# PIR_Sensor.net
KiCad netlist of a schematic drawn in Altium Designer
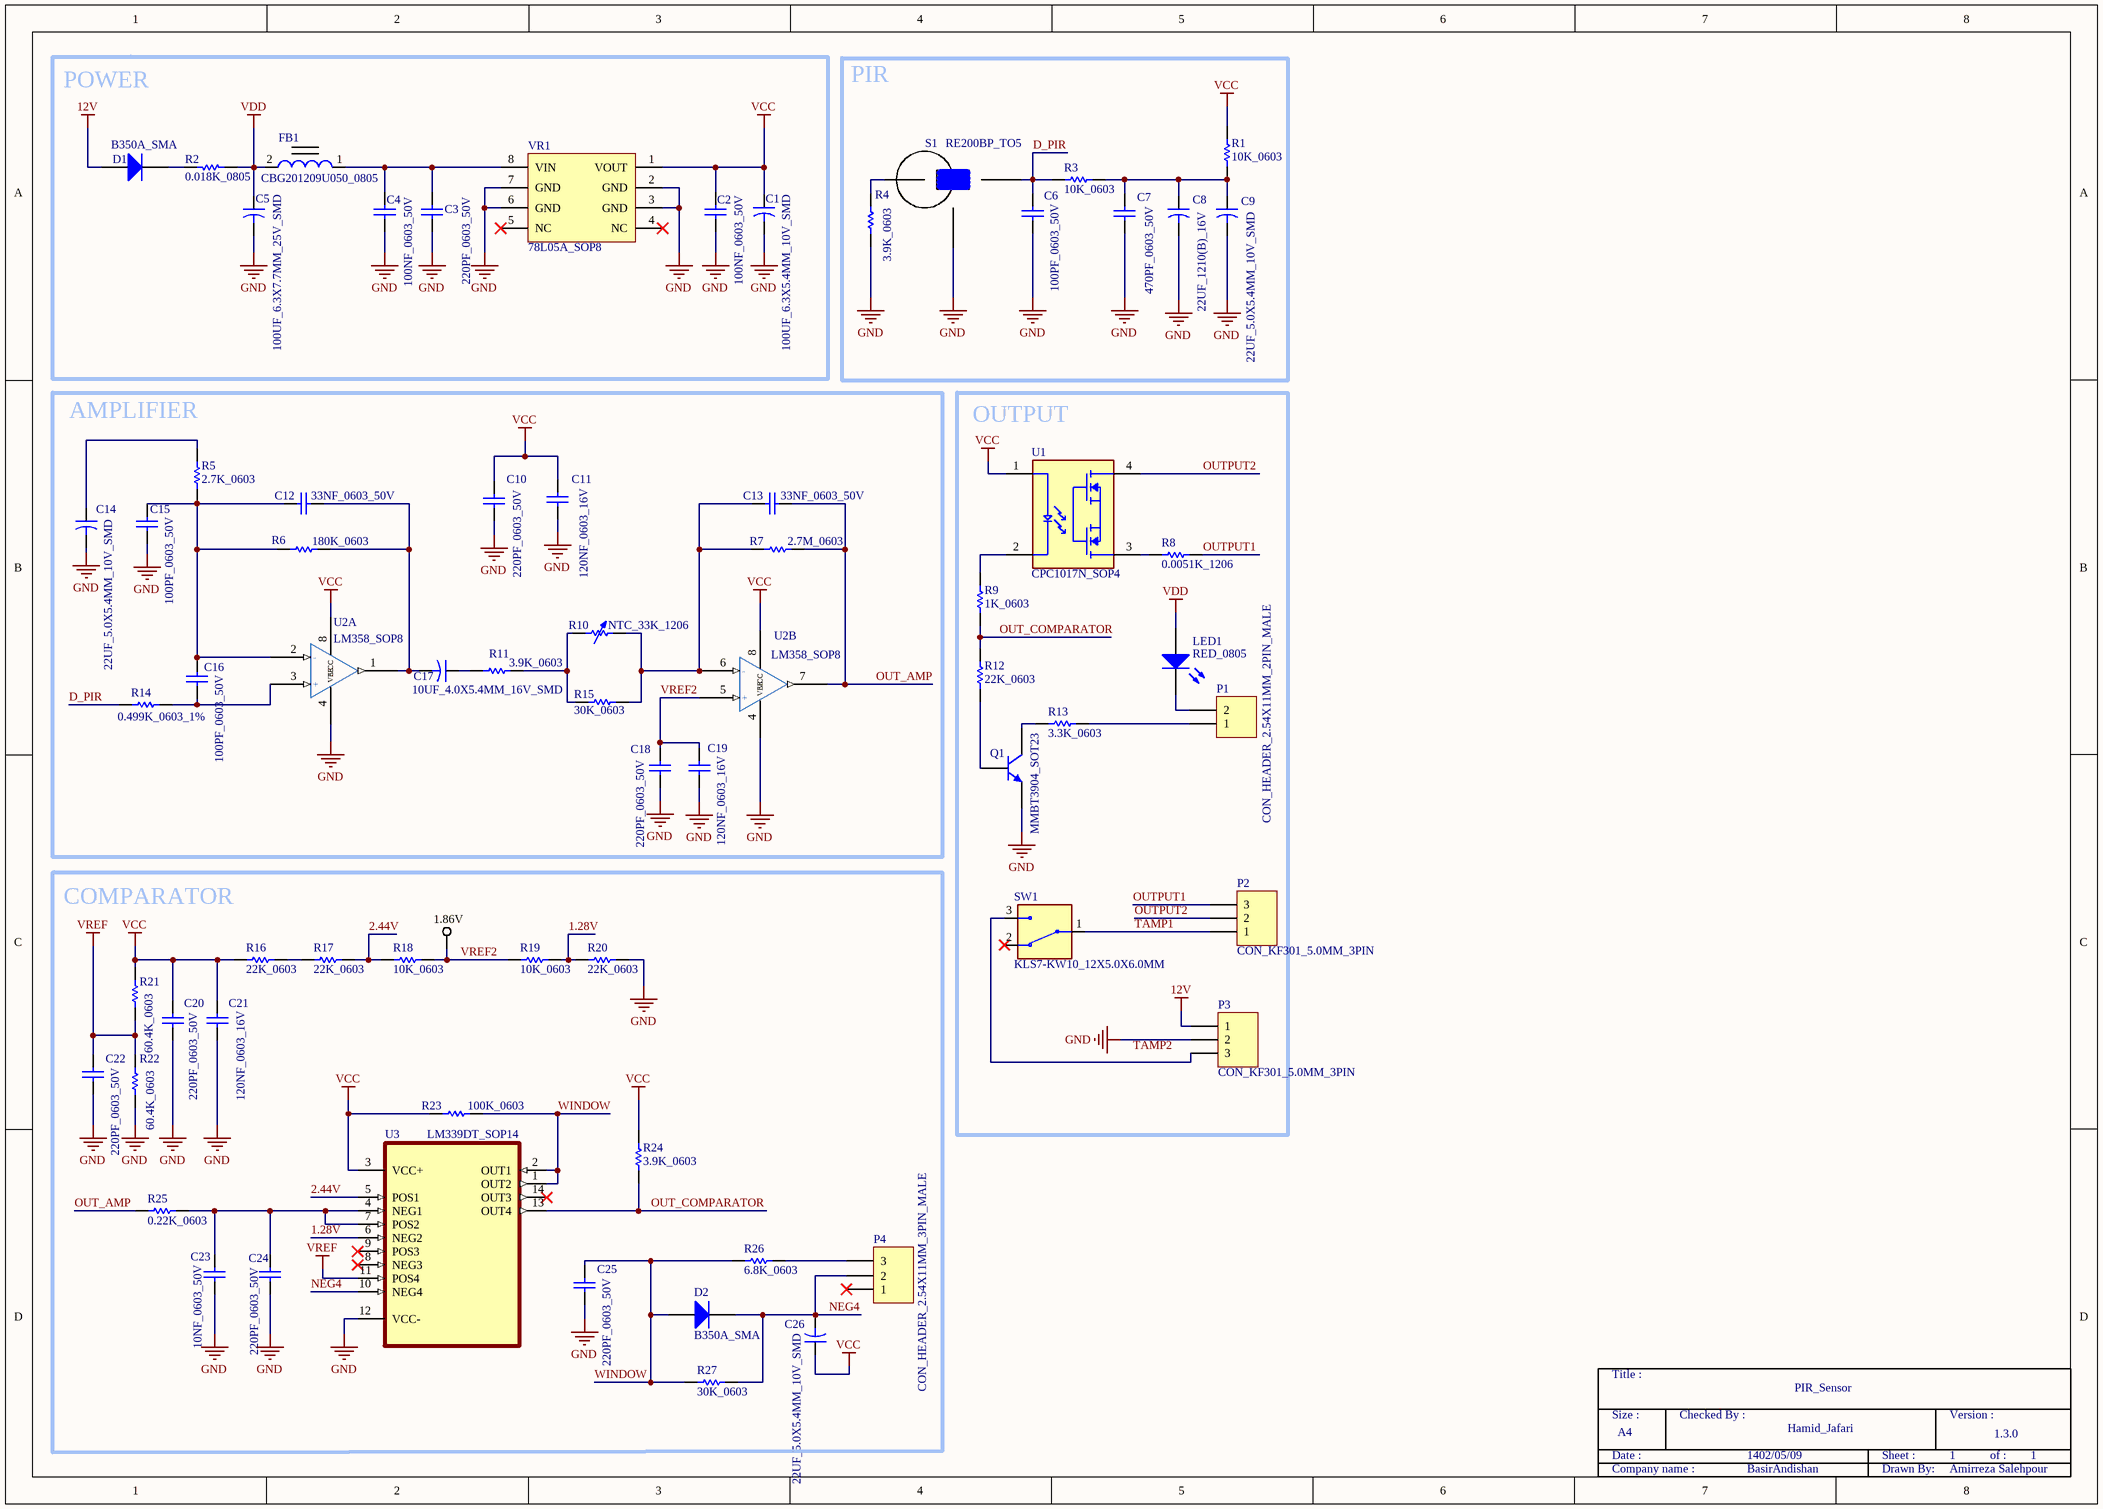
[diagram p0: PIR_Sensor.SchDoc]

(export (version "E")
  (design (tool "Eeschema 10.0.6"))
  (components
    (comp (ref "1.86V")
      (value "TESTPOINT_SMD")
      (footprint "TPSMD_C1")
      (description "TEST POINT")
      (fields (field (name "MANF") "MANF") (field (name "MANF_P#") "MANF_P#"))
      (libsource (lib "GTC Shem") (part "TESTPOINT_SMD"))
    )
    (comp (ref "C1")
      (value "100UF_6.3X5.4MM_10V_SMD")
      (footprint "CAP_EL_SMD_6X8")
      (libsource (lib "GTC Shem") (part "Cap_Electrical"))
    )
    (comp (ref "C2")
      (value "100NF_0603_50V")
      (footprint "Cap_0603_Nominal")
      (description "0603")
      (libsource (lib "GTC Shem") (part "Cap"))
    )
    (comp (ref "C3")
      (value "220PF_0603_50V")
      (footprint "Cap_0603_Nominal")
      (description "0603")
      (libsource (lib "GTC Shem") (part "Cap"))
    )
    (comp (ref "C4")
      (value "100NF_0603_50V")
      (footprint "Cap_0603_Nominal")
      (description "0603")
      (libsource (lib "GTC Shem") (part "Cap"))
    )
    (comp (ref "C5")
      (value "100UF_6.3X7.7MM_25V_SMD")
      (footprint "CAP_EL_SMD_6X8")
      (libsource (lib "GTC Shem") (part "Cap_Electrical"))
    )
    (comp (ref "C6")
      (value "100PF_0603_50V")
      (footprint "Cap_0603_Nominal")
      (description "0603")
      (libsource (lib "GTC Shem") (part "Cap"))
    )
    (comp (ref "C7")
      (value "470PF_0603_50V")
      (footprint "Cap_0603_Nominal")
      (description "0603")
      (libsource (lib "GTC Shem") (part "Cap"))
    )
    (comp (ref "C8")
      (value "22UF_1210(B)_16V")
      (footprint "Cap_Tantal(3528)_B")
      (description "Tant")
      (libsource (lib "GTC Shem") (part "Cap_Electrical"))
    )
    (comp (ref "C9")
      (value "22UF_5.0X5.4MM_10V_SMD")
      (footprint "CAP_EL_SMD_5")
      (libsource (lib "GTC Shem") (part "Cap_Electrical"))
    )
    (comp (ref "C10")
      (value "220PF_0603_50V")
      (footprint "Cap_0603_Nominal")
      (description "0603")
      (libsource (lib "GTC Shem") (part "Cap"))
    )
    (comp (ref "C11")
      (value "120NF_0603_16V")
      (footprint "Cap_0603_Nominal")
      (description "0603")
      (libsource (lib "GTC Shem") (part "Cap"))
    )
    (comp (ref "C12")
      (value "33NF_0603_50V")
      (footprint "Cap_0603_Nominal")
      (description "0603")
      (libsource (lib "GTC Shem") (part "Cap"))
    )
    (comp (ref "C13")
      (value "33NF_0603_50V")
      (footprint "Cap_0603_Nominal")
      (description "0603")
      (libsource (lib "GTC Shem") (part "Cap"))
    )
    (comp (ref "C14")
      (value "22UF_5.0X5.4MM_10V_SMD")
      (footprint "CAP_EL_SMD_5")
      (libsource (lib "GTC Shem") (part "Cap_Electrical"))
    )
    (comp (ref "C15")
      (value "100PF_0603_50V")
      (footprint "Cap_0603_Nominal")
      (description "0603")
      (libsource (lib "GTC Shem") (part "Cap"))
    )
    (comp (ref "C16")
      (value "100PF_0603_50V")
      (footprint "Cap_0603_Nominal")
      (description "0603")
      (libsource (lib "GTC Shem") (part "Cap"))
    )
    (comp (ref "C17")
      (value "10UF_4.0X5.4MM_16V_SMD")
      (footprint "CAP_EL_SMD_4")
      (libsource (lib "GTC Shem") (part "Cap_Electrical"))
    )
    (comp (ref "C18")
      (value "220PF_0603_50V")
      (footprint "Cap_0603_Nominal")
      (description "0603")
      (libsource (lib "GTC Shem") (part "Cap"))
    )
    (comp (ref "C19")
      (value "120NF_0603_16V")
      (footprint "Cap_0603_Nominal")
      (description "0603")
      (libsource (lib "GTC Shem") (part "Cap"))
    )
    (comp (ref "C20")
      (value "220PF_0603_50V")
      (footprint "Cap_0603_Nominal")
      (description "0603")
      (libsource (lib "GTC Shem") (part "Cap"))
    )
    (comp (ref "C21")
      (value "120NF_0603_16V")
      (footprint "Cap_0603_Nominal")
      (description "0603")
      (libsource (lib "GTC Shem") (part "Cap"))
    )
    (comp (ref "C22")
      (value "220PF_0603_50V")
      (footprint "Cap_0603_Nominal")
      (description "0603")
      (libsource (lib "GTC Shem") (part "Cap"))
    )
    (comp (ref "C23")
      (value "10NF_0603_50V")
      (footprint "Cap_0603_Nominal")
      (description "0603")
      (libsource (lib "GTC Shem") (part "Cap"))
    )
    (comp (ref "C24")
      (value "220PF_0603_50V")
      (footprint "Cap_0603_Nominal")
      (description "0603")
      (libsource (lib "GTC Shem") (part "Cap"))
    )
    (comp (ref "C25")
      (value "220PF_0603_50V")
      (footprint "Cap_0603_Nominal")
      (description "0603")
      (libsource (lib "GTC Shem") (part "Cap"))
    )
    (comp (ref "C26")
      (value "22UF_5.0X5.4MM_10V_SMD")
      (footprint "CAP_EL_SMD_5")
      (libsource (lib "GTC Shem") (part "Cap_Electrical"))
    )
    (comp (ref "D1")
      (value "B350A_SMA")
      (footprint "DIODE_SMA")
      (description "B350A")
      (libsource (lib "GTC Shem") (part "Diode"))
    )
    (comp (ref "D2")
      (value "B350A_SMA")
      (footprint "DIODE_SMA")
      (description "B350A")
      (libsource (lib "GTC Shem") (part "Diode"))
    )
    (comp (ref "FB1")
      (value "CBG201209U050_0805")
      (footprint "INDUCTOR_0805_Nominal")
      (libsource (lib "GTC Shem") (part "FERRITE BEAD"))
    )
    (comp (ref "LED1")
      (value "RED_0805")
      (footprint "LED_0805_NOMINAL")
      (libsource (lib "GTC Shem") (part "LED"))
    )
    (comp (ref "P1")
      (value "CON_HEADER_2.54X11MM_2PIN_MALE")
      (footprint "HDR_M_1X2_2.54mm")
      (description "Header, 2-Pin")
      (fields (field (name "PUBLISHER") "Altium Limited"))
      (libsource (lib "GTC Shem") (part "Header 2"))
    )
    (comp (ref "P2")
      (value "CON_KF301_5.0MM_3PIN")
      (footprint "CON_KF301_5MM_3PIN")
      (libsource (lib "GTC Shem") (part "Con_3PIN"))
    )
    (comp (ref "P3")
      (value "CON_KF301_5.0MM_3PIN")
      (footprint "CON_KF301_5MM_3PIN")
      (libsource (lib "") (part "Con_3PIN_1"))
    )
    (comp (ref "P4")
      (value "CON_HEADER_2.54X11MM_3PIN_MALE")
      (footprint "HDR_M_1X3_2.54mm")
      (description "Header,3-Pin")
      (fields (field (name "PUBLISHER") "Altium Limited"))
      (libsource (lib "GTC Shem") (part "Header 3"))
    )
    (comp (ref "Q1")
      (value "MMBT3904_SOT23")
      (footprint "SOT23_BJT")
      (libsource (lib "GTC Shem") (part "MMBT3904"))
    )
    (comp (ref "R1")
      (value "10K_0603")
      (footprint "Res_0603_Nominal")
      (description "0603")
      (libsource (lib "GTC Shem") (part "RES"))
    )
    (comp (ref "R2")
      (value "0.018K_0805")
      (footprint "Res_0805_Nominal")
      (description "0805")
      (libsource (lib "GTC Shem") (part "RES"))
    )
    (comp (ref "R3")
      (value "10K_0603")
      (footprint "Res_0603_Nominal")
      (description "0603")
      (libsource (lib "GTC Shem") (part "RES"))
    )
    (comp (ref "R4")
      (value "3.9K_0603")
      (footprint "Res_0603_Nominal")
      (description "0603")
      (libsource (lib "GTC Shem") (part "RES"))
    )
    (comp (ref "R5")
      (value "2.7K_0603")
      (footprint "Res_0603_Nominal")
      (description "0603")
      (libsource (lib "GTC Shem") (part "RES"))
    )
    (comp (ref "R6")
      (value "180K_0603")
      (footprint "Res_0603_Nominal")
      (description "0603")
      (libsource (lib "GTC Shem") (part "RES"))
    )
    (comp (ref "R7")
      (value "2.7M_0603")
      (footprint "Res_0603_Nominal")
      (description "0603")
      (libsource (lib "GTC Shem") (part "RES"))
    )
    (comp (ref "R8")
      (value "0.0051K_1206")
      (footprint "Res_1206_NOMINAL")
      (description "0603")
      (libsource (lib "GTC Shem") (part "RES"))
    )
    (comp (ref "R9")
      (value "1K_0603")
      (footprint "Res_0603_Nominal")
      (description "0603")
      (libsource (lib "GTC Shem") (part "RES"))
    )
    (comp (ref "R10")
      (value "NTC_33K_1206")
      (footprint "Res_1206_NOMINAL")
      (description "Variable Resistor")
      (fields (field (name "PUBLISHER") "Altium Limited"))
      (libsource (lib "Miscellaneous Devices") (part "Res Adj1"))
    )
    (comp (ref "R11")
      (value "3.9K_0603")
      (footprint "Res_0603_Nominal")
      (description "0603")
      (libsource (lib "GTC Shem") (part "RES"))
    )
    (comp (ref "R12")
      (value "22K_0603")
      (footprint "Res_0603_Nominal")
      (description "0603")
      (libsource (lib "GTC Shem") (part "RES"))
    )
    (comp (ref "R13")
      (value "3.3K_0603")
      (footprint "Res_0603_Nominal")
      (description "0603")
      (libsource (lib "GTC Shem") (part "RES"))
    )
    (comp (ref "R14")
      (value "0.499K_0603_1%")
      (footprint "Res_0603_Nominal")
      (description "0603")
      (libsource (lib "GTC Shem") (part "RES"))
    )
    (comp (ref "R15")
      (value "30K_0603")
      (footprint "Res_0603_Nominal")
      (description "0603")
      (libsource (lib "GTC Shem") (part "RES"))
    )
    (comp (ref "R16")
      (value "22K_0603")
      (footprint "Res_0603_Nominal")
      (description "0603")
      (libsource (lib "GTC Shem") (part "RES"))
    )
    (comp (ref "R17")
      (value "22K_0603")
      (footprint "Res_0603_Nominal")
      (description "0603")
      (libsource (lib "GTC Shem") (part "RES"))
    )
    (comp (ref "R18")
      (value "10K_0603")
      (footprint "Res_0603_Nominal")
      (description "0603")
      (libsource (lib "GTC Shem") (part "RES"))
    )
    (comp (ref "R19")
      (value "10K_0603")
      (footprint "Res_0603_Nominal")
      (description "0603")
      (libsource (lib "GTC Shem") (part "RES"))
    )
    (comp (ref "R20")
      (value "22K_0603")
      (footprint "Res_0603_Nominal")
      (description "0603")
      (libsource (lib "GTC Shem") (part "RES"))
    )
    (comp (ref "R21")
      (value "60.4K_0603")
      (footprint "Res_0603_Nominal")
      (description "0603")
      (libsource (lib "GTC Shem") (part "RES"))
    )
    (comp (ref "R22")
      (value "60.4K_0603")
      (footprint "Res_0603_Nominal")
      (description "0603")
      (libsource (lib "GTC Shem") (part "RES"))
    )
    (comp (ref "R23")
      (value "100K_0603")
      (footprint "Res_0603_Nominal")
      (description "0603")
      (libsource (lib "GTC Shem") (part "RES"))
    )
    (comp (ref "R24")
      (value "3.9K_0603")
      (footprint "Res_0603_Nominal")
      (description "0603")
      (libsource (lib "GTC Shem") (part "RES"))
    )
    (comp (ref "R25")
      (value "0.22K_0603")
      (footprint "Res_0603_Nominal")
      (description "0603")
      (libsource (lib "GTC Shem") (part "RES"))
    )
    (comp (ref "R26")
      (value "6.8K_0603")
      (footprint "Res_0603_Nominal")
      (description "0603")
      (libsource (lib "GTC Shem") (part "RES"))
    )
    (comp (ref "R27")
      (value "30K_0603")
      (footprint "Res_0603_Nominal")
      (description "0603")
      (libsource (lib "GTC Shem") (part "RES"))
    )
    (comp (ref "S1")
      (value "RE200BP_TO5")
      (footprint "SENSOR_PIR_TO39")
      (libsource (lib "GTC Shem") (part "PIR_Sensor"))
    )
    (comp (ref "SW1")
      (value "KLS7-KW10_12X5.0X6.0MM")
      (footprint "SW_KLS7-KW10")
      (description "SWITCH SNAP ACTION SPDT 2A 125V")
      (fields (field (name "MF") "E-Switch") (field (name "MP") "MS0850502F030P1A"))
      (libsource (lib "GTC Schematic") (part "Micro switch"))
    )
    (comp (ref "U1")
      (value "CPC1017N_SOP4")
      (footprint "SOIC254P610X218-4N")
      (description "Solid State SPST-NO _1 Form A_ 4-SOP _0.150, 3.81mm_")
      (fields (field (name "MP") "CPC1017N") (field (name "MF") "IXYS Integrated"))
      (libsource (lib "CPC1017N") (part "CPC1017N"))
    )
    (comp (ref "U2") (value "LM358_SOP8") (footprint "SOIC8") (libsource (lib "GTC Shem") (part "LM358")))
    (comp (ref "U3")
      (value "LM339DT_SOP14")
      (footprint "SO_14")
      (description "LM339 Series Quad 32 V 250 nA SMT Low Power Voltage Comparator - SOIC-14")
      (fields (field (name "MF") "STMicroelectronics") (field (name "MP") "LM339DT"))
      (libsource (lib "LM339DT") (part "LM339DT"))
    )
    (comp (ref "VR1") (value "78L05A_SOP8") (footprint "SOP8") (libsource (lib "GTC Shem") (part "78L05A")))
  )
  (nets
    (net (code "1") (name "/1.28V") (class "Default")
      (node (ref "R19") (pin "2") (pinfunction "2_2") (pintype "passive"))
      (node (ref "R20") (pin "1") (pinfunction "1_1") (pintype "passive"))
      (node (ref "U3") (pin "6") (pinfunction "NEG2_6") (pintype "input"))
    )
    (net (code "2") (name "/2.44V") (class "Default")
      (node (ref "R17") (pin "1") (pinfunction "1_1") (pintype "passive"))
      (node (ref "R18") (pin "1") (pinfunction "1_1") (pintype "passive"))
      (node (ref "U3") (pin "5") (pinfunction "POS1_5") (pintype "input"))
    )
    (net (code "4") (name "/D_PIR") (class "Default")
      (node (ref "C6") (pin "2") (pinfunction "2_2") (pintype "passive"))
      (node (ref "R14") (pin "2") (pinfunction "2_2") (pintype "passive"))
      (node (ref "R3") (pin "2") (pinfunction "2_2") (pintype "passive"))
      (node (ref "S1") (pin "1") (pinfunction "1_1") (pintype "passive"))
    )
    (net (code "5") (name "/NEG4") (class "Default")
      (node (ref "C26") (pin "2") (pinfunction "2_2") (pintype "passive"))
      (node (ref "D2") (pin "2") (pinfunction "K_2") (pintype "passive"))
      (node (ref "P4") (pin "2") (pinfunction "2_2") (pintype "passive"))
      (node (ref "R27") (pin "2") (pinfunction "2_2") (pintype "passive"))
      (node (ref "U3") (pin "10") (pinfunction "NEG4_10") (pintype "input"))
    )
    (net (code "6") (name "/OUTPUT1") (class "Default")
      (node (ref "P2") (pin "3") (pinfunction "3_3") (pintype "passive"))
      (node (ref "R8") (pin "2") (pinfunction "2_2") (pintype "passive"))
    )
    (net (code "7") (name "/OUTPUT2") (class "Default")
      (node (ref "P2") (pin "2") (pinfunction "2_2") (pintype "passive"))
      (node (ref "U1") (pin "4") (pinfunction "LOAD2_4") (pintype "passive"))
    )
    (net (code "8") (name "/OUT_AMP") (class "Default")
      (node (ref "C13") (pin "1") (pinfunction "1_1") (pintype "passive"))
      (node (ref "R25") (pin "2") (pinfunction "2_2") (pintype "passive"))
      (node (ref "R7") (pin "1") (pinfunction "1_1") (pintype "passive"))
      (node (ref "U2") (pin "7") (pinfunction "OUT_7") (pintype "output"))
    )
    (net (code "9") (name "/OUT_COMPARATOR") (class "Default")
      (node (ref "R12") (pin "2") (pinfunction "2_2") (pintype "passive"))
      (node (ref "R24") (pin "2") (pinfunction "2_2") (pintype "passive"))
      (node (ref "R9") (pin "1") (pinfunction "1_1") (pintype "passive"))
      (node (ref "U3") (pin "13") (pinfunction "OUT4_13") (pintype "output"))
    )
    (net (code "10") (name "/TAMP1") (class "Default")
      (node (ref "P2") (pin "1") (pinfunction "1_1") (pintype "passive"))
      (node (ref "SW1") (pin "1") (pinfunction "COM_1") (pintype "passive"))
    )
    (net (code "12") (name "/VREF2") (class "Default")
      (node (ref "1.86V") (pin "1") (pinfunction "1_1") (pintype "passive"))
      (node (ref "C18") (pin "2") (pinfunction "2_2") (pintype "passive"))
      (node (ref "C19") (pin "2") (pinfunction "2_2") (pintype "passive"))
      (node (ref "R18") (pin "2") (pinfunction "2_2") (pintype "passive"))
      (node (ref "R19") (pin "1") (pinfunction "1_1") (pintype "passive"))
      (node (ref "U2") (pin "5") (pinfunction "+_5") (pintype "input"))
    )
    (net (code "13") (name "/WINDOW") (class "Default")
      (node (ref "C25") (pin "1") (pinfunction "1_1") (pintype "passive"))
      (node (ref "D2") (pin "1") (pinfunction "A_1") (pintype "passive"))
      (node (ref "R23") (pin "1") (pinfunction "1_1") (pintype "passive"))
      (node (ref "R26") (pin "1") (pinfunction "1_1") (pintype "passive"))
      (node (ref "R27") (pin "1") (pinfunction "1_1") (pintype "passive"))
      (node (ref "U3") (pin "1") (pinfunction "OUT2_1") (pintype "output"))
      (node (ref "U3") (pin "2") (pinfunction "OUT1_2") (pintype "input"))
    )
    (net (code "14") (name "12V") (class "Default")
      (node (ref "D1") (pin "1") (pinfunction "A_1") (pintype "passive"))
      (node (ref "P3") (pin "1") (pinfunction "1_1") (pintype "passive"))
    )
    (net (code "15") (name "GND") (class "Default")
      (node (ref "C1") (pin "2") (pinfunction "2_2") (pintype "passive"))
      (node (ref "C10") (pin "1") (pinfunction "1_1") (pintype "passive"))
      (node (ref "C11") (pin "1") (pinfunction "1_1") (pintype "passive"))
      (node (ref "C14") (pin "2") (pinfunction "2_2") (pintype "passive"))
      (node (ref "C15") (pin "2") (pinfunction "2_2") (pintype "passive"))
      (node (ref "C18") (pin "1") (pinfunction "1_1") (pintype "passive"))
      (node (ref "C19") (pin "1") (pinfunction "1_1") (pintype "passive"))
      (node (ref "C2") (pin "1") (pinfunction "1_1") (pintype "passive"))
      (node (ref "C20") (pin "1") (pinfunction "1_1") (pintype "passive"))
      (node (ref "C21") (pin "1") (pinfunction "1_1") (pintype "passive"))
      (node (ref "C22") (pin "1") (pinfunction "1_1") (pintype "passive"))
      (node (ref "C23") (pin "1") (pinfunction "1_1") (pintype "passive"))
      (node (ref "C24") (pin "1") (pinfunction "1_1") (pintype "passive"))
      (node (ref "C25") (pin "2") (pinfunction "2_2") (pintype "passive"))
      (node (ref "C3") (pin "1") (pinfunction "1_1") (pintype "passive"))
      (node (ref "C4") (pin "1") (pinfunction "1_1") (pintype "passive"))
      (node (ref "C5") (pin "2") (pinfunction "2_2") (pintype "passive"))
      (node (ref "C6") (pin "1") (pinfunction "1_1") (pintype "passive"))
      (node (ref "C7") (pin "1") (pinfunction "1_1") (pintype "passive"))
      (node (ref "C8") (pin "2") (pinfunction "2_2") (pintype "passive"))
      (node (ref "C9") (pin "2") (pinfunction "2_2") (pintype "passive"))
      (node (ref "P3") (pin "2") (pinfunction "2_2") (pintype "passive"))
      (node (ref "Q1") (pin "2") (pinfunction "E_2") (pintype "passive"))
      (node (ref "R20") (pin "2") (pinfunction "2_2") (pintype "passive"))
      (node (ref "R22") (pin "2") (pinfunction "2_2") (pintype "passive"))
      (node (ref "R4") (pin "1") (pinfunction "1_1") (pintype "passive"))
      (node (ref "S1") (pin "3") (pinfunction "3_3") (pintype "passive"))
      (node (ref "U2") (pin "4") (pinfunction "VEE_4") (pintype "passive"))
      (node (ref "U3") (pin "12") (pinfunction "VCC-_12") (pintype "power_in"))
      (node (ref "VR1") (pin "2") (pinfunction "GND_2") (pintype "passive"))
      (node (ref "VR1") (pin "3") (pinfunction "GND_3") (pintype "passive"))
      (node (ref "VR1") (pin "6") (pinfunction "GND_6") (pintype "passive"))
      (node (ref "VR1") (pin "7") (pinfunction "GND_7") (pintype "passive"))
    )
    (net (code "16") (name "Net-(C7-Pad2)") (class "Default")
      (node (ref "C7") (pin "2") (pinfunction "2_2") (pintype "passive"))
      (node (ref "C8") (pin "1") (pinfunction "1_1") (pintype "passive"))
      (node (ref "C9") (pin "1") (pinfunction "1_1") (pintype "passive"))
      (node (ref "R1") (pin "1") (pinfunction "1_1") (pintype "passive"))
      (node (ref "R3") (pin "1") (pinfunction "1_1") (pintype "passive"))
    )
    (net (code "17") (name "Net-(C14-Pad1)") (class "Default")
      (node (ref "C14") (pin "1") (pinfunction "1_1") (pintype "passive"))
      (node (ref "R5") (pin "2") (pinfunction "2_2") (pintype "passive"))
    )
    (net (code "18") (name "Net-(C17-Pad1)") (class "Default")
      (node (ref "C17") (pin "1") (pinfunction "1_1") (pintype "passive"))
      (node (ref "R11") (pin "2") (pinfunction "2_2") (pintype "passive"))
    )
    (net (code "19") (name "Net-(D1-K)") (class "Default")
      (node (ref "D1") (pin "2") (pinfunction "K_2") (pintype "passive"))
      (node (ref "R2") (pin "2") (pinfunction "2_2") (pintype "passive"))
    )
    (net (code "20") (name "Net-(LED1-K)") (class "Default")
      (node (ref "LED1") (pin "2") (pinfunction "K_2") (pintype "passive"))
      (node (ref "P1") (pin "2") (pinfunction "2_2") (pintype "passive"))
    )
    (net (code "21") (name "Net-(P1-Pad1)") (class "Default")
      (node (ref "P1") (pin "1") (pinfunction "1_1") (pintype "passive"))
      (node (ref "R13") (pin "1") (pinfunction "1_1") (pintype "passive"))
    )
    (net (code "22") (name "Net-(P4-Pad3)") (class "Default")
      (node (ref "P4") (pin "3") (pinfunction "3_3") (pintype "passive"))
      (node (ref "R26") (pin "2") (pinfunction "2_2") (pintype "passive"))
    )
    (net (code "23") (name "Net-(Q1-B)") (class "Default")
      (node (ref "Q1") (pin "1") (pinfunction "B_1") (pintype "passive"))
      (node (ref "R12") (pin "1") (pinfunction "1_1") (pintype "passive"))
    )
    (net (code "24") (name "Net-(Q1-C)") (class "Default")
      (node (ref "Q1") (pin "3") (pinfunction "C_3") (pintype "passive"))
      (node (ref "R13") (pin "2") (pinfunction "2_2") (pintype "passive"))
    )
    (net (code "25") (name "Net-(R4-Pad2)") (class "Default")
      (node (ref "R4") (pin "2") (pinfunction "2_2") (pintype "passive"))
      (node (ref "S1") (pin "2") (pinfunction "2_2") (pintype "passive"))
    )
    (net (code "26") (name "Net-(R10-Pad1)") (class "Default")
      (node (ref "R10") (pin "1") (pinfunction "1_1") (pintype "passive"))
      (node (ref "R11") (pin "1") (pinfunction "1_1") (pintype "passive"))
      (node (ref "R15") (pin "2") (pinfunction "2_2") (pintype "passive"))
    )
    (net (code "27") (name "Net-(R16-Pad1)") (class "Default")
      (node (ref "R16") (pin "1") (pinfunction "1_1") (pintype "passive"))
      (node (ref "R17") (pin "2") (pinfunction "2_2") (pintype "passive"))
    )
    (net (code "28") (name "Net-(SW1-NO)") (class "Default")
      (node (ref "P3") (pin "3") (pinfunction "3_3") (pintype "passive"))
      (node (ref "SW1") (pin "3") (pinfunction "NO_3") (pintype "passive"))
    )
    (net (code "29") (name "Net-(U1--CONTROL)") (class "Default")
      (node (ref "R9") (pin "2") (pinfunction "2_2") (pintype "passive"))
      (node (ref "U1") (pin "2") (pinfunction "-CONTROL_2") (pintype "passive"))
    )
    (net (code "30") (name "Net-(U1-LOAD1)") (class "Default")
      (node (ref "R8") (pin "1") (pinfunction "1_1") (pintype "passive"))
      (node (ref "U1") (pin "3") (pinfunction "LOAD1_3") (pintype "passive"))
    )
    (net (code "31") (name "Net-(U2A-+)") (class "Default")
      (node (ref "C16") (pin "1") (pinfunction "1_1") (pintype "passive"))
      (node (ref "R14") (pin "1") (pinfunction "1_1") (pintype "passive"))
      (node (ref "U2") (pin "3") (pinfunction "+_3") (pintype "input"))
    )
    (net (code "32") (name "Net-(U2A--)") (class "Default")
      (node (ref "C12") (pin "2") (pinfunction "2_2") (pintype "passive"))
      (node (ref "C15") (pin "1") (pinfunction "1_1") (pintype "passive"))
      (node (ref "C16") (pin "2") (pinfunction "2_2") (pintype "passive"))
      (node (ref "R5") (pin "1") (pinfunction "1_1") (pintype "passive"))
      (node (ref "R6") (pin "2") (pinfunction "2_2") (pintype "passive"))
      (node (ref "U2") (pin "2") (pinfunction "-_2") (pintype "input"))
    )
    (net (code "33") (name "Net-(U2A-OUT)") (class "Default")
      (node (ref "C12") (pin "1") (pinfunction "1_1") (pintype "passive"))
      (node (ref "C17") (pin "2") (pinfunction "2_2") (pintype "passive"))
      (node (ref "R6") (pin "1") (pinfunction "1_1") (pintype "passive"))
      (node (ref "U2") (pin "1") (pinfunction "OUT_1") (pintype "output"))
    )
    (net (code "34") (name "Net-(U2B--)") (class "Default")
      (node (ref "C13") (pin "2") (pinfunction "2_2") (pintype "passive"))
      (node (ref "R10") (pin "2") (pinfunction "2_2") (pintype "passive"))
      (node (ref "R15") (pin "1") (pinfunction "1_1") (pintype "passive"))
      (node (ref "R7") (pin "2") (pinfunction "2_2") (pintype "passive"))
      (node (ref "U2") (pin "6") (pinfunction "-_6") (pintype "input"))
    )
    (net (code "35") (name "Net-(U3-NEG1)") (class "Default")
      (node (ref "C23") (pin "2") (pinfunction "2_2") (pintype "passive"))
      (node (ref "C24") (pin "2") (pinfunction "2_2") (pintype "passive"))
      (node (ref "R25") (pin "1") (pinfunction "1_1") (pintype "passive"))
      (node (ref "U3") (pin "4") (pinfunction "NEG1_4") (pintype "input"))
      (node (ref "U3") (pin "7") (pinfunction "POS2_7") (pintype "input"))
    )
    (net (code "36") (name "Net-(VR1-VIN)") (class "Default")
      (node (ref "C3") (pin "2") (pinfunction "2_2") (pintype "passive"))
      (node (ref "C4") (pin "2") (pinfunction "2_2") (pintype "passive"))
      (node (ref "FB1") (pin "1") (pinfunction "1_1") (pintype "passive"))
      (node (ref "VR1") (pin "8") (pinfunction "VIN_8") (pintype "passive"))
    )
    (net (code "37") (name "VCC") (class "Default")
      (node (ref "C1") (pin "1") (pinfunction "1_1") (pintype "passive"))
      (node (ref "C10") (pin "2") (pinfunction "2_2") (pintype "passive"))
      (node (ref "C11") (pin "2") (pinfunction "2_2") (pintype "passive"))
      (node (ref "C2") (pin "2") (pinfunction "2_2") (pintype "passive"))
      (node (ref "C20") (pin "2") (pinfunction "2_2") (pintype "passive"))
      (node (ref "C21") (pin "2") (pinfunction "2_2") (pintype "passive"))
      (node (ref "C26") (pin "1") (pinfunction "1_1") (pintype "passive"))
      (node (ref "R1") (pin "2") (pinfunction "2_2") (pintype "passive"))
      (node (ref "R16") (pin "2") (pinfunction "2_2") (pintype "passive"))
      (node (ref "R21") (pin "1") (pinfunction "1_1") (pintype "passive"))
      (node (ref "R23") (pin "2") (pinfunction "2_2") (pintype "passive"))
      (node (ref "R24") (pin "1") (pinfunction "1_1") (pintype "passive"))
      (node (ref "U1") (pin "1") (pinfunction "+CONTROL_1") (pintype "passive"))
      (node (ref "U2") (pin "8") (pinfunction "VCC_8") (pintype "passive"))
      (node (ref "U3") (pin "3") (pinfunction "VCC+_3") (pintype "power_in"))
      (node (ref "VR1") (pin "1") (pinfunction "VOUT_1") (pintype "passive"))
    )
    (net (code "38") (name "VDD") (class "Default")
      (node (ref "C5") (pin "1") (pinfunction "1_1") (pintype "passive"))
      (node (ref "FB1") (pin "2") (pinfunction "2_2") (pintype "passive"))
      (node (ref "LED1") (pin "1") (pinfunction "A_1") (pintype "passive"))
      (node (ref "R2") (pin "1") (pinfunction "1_1") (pintype "passive"))
    )
    (net (code "39") (name "VREF") (class "Default")
      (node (ref "C22") (pin "2") (pinfunction "2_2") (pintype "passive"))
      (node (ref "R21") (pin "2") (pinfunction "2_2") (pintype "passive"))
      (node (ref "R22") (pin "1") (pinfunction "1_1") (pintype "passive"))
      (node (ref "U3") (pin "11") (pinfunction "POS4_11") (pintype "input"))
    )
    (net (code "40") (name "unconnected-(P4-Pad1)") (class "Default")
      (node (ref "P4") (pin "1") (pinfunction "1_1") (pintype "passive+no_connect"))
    )
    (net (code "41") (name "unconnected-(SW1-NC-Pad2)") (class "Default")
      (node (ref "SW1") (pin "2") (pinfunction "NC_2") (pintype "passive+no_connect"))
    )
    (net (code "42") (name "unconnected-(U3-NEG3-Pad8)") (class "Default")
      (node (ref "U3") (pin "8") (pinfunction "NEG3_8") (pintype "input+no_connect"))
    )
    (net (code "43") (name "unconnected-(U3-OUT3-Pad14)") (class "Default")
      (node (ref "U3") (pin "14") (pinfunction "OUT3_14") (pintype "output+no_connect"))
    )
    (net (code "44") (name "unconnected-(U3-POS3-Pad9)") (class "Default")
      (node (ref "U3") (pin "9") (pinfunction "POS3_9") (pintype "input+no_connect"))
    )
    (net (code "45") (name "unconnected-(VR1-NC-Pad4)") (class "Default")
      (node (ref "VR1") (pin "4") (pinfunction "NC_4") (pintype "passive+no_connect"))
    )
    (net (code "46") (name "unconnected-(VR1-NC-Pad5)") (class "Default")
      (node (ref "VR1") (pin "5") (pinfunction "NC_5") (pintype "passive+no_connect"))
    )
  )
)
